# psg-dual.net
KiCad netlist of a schematic drawn in EAGLE
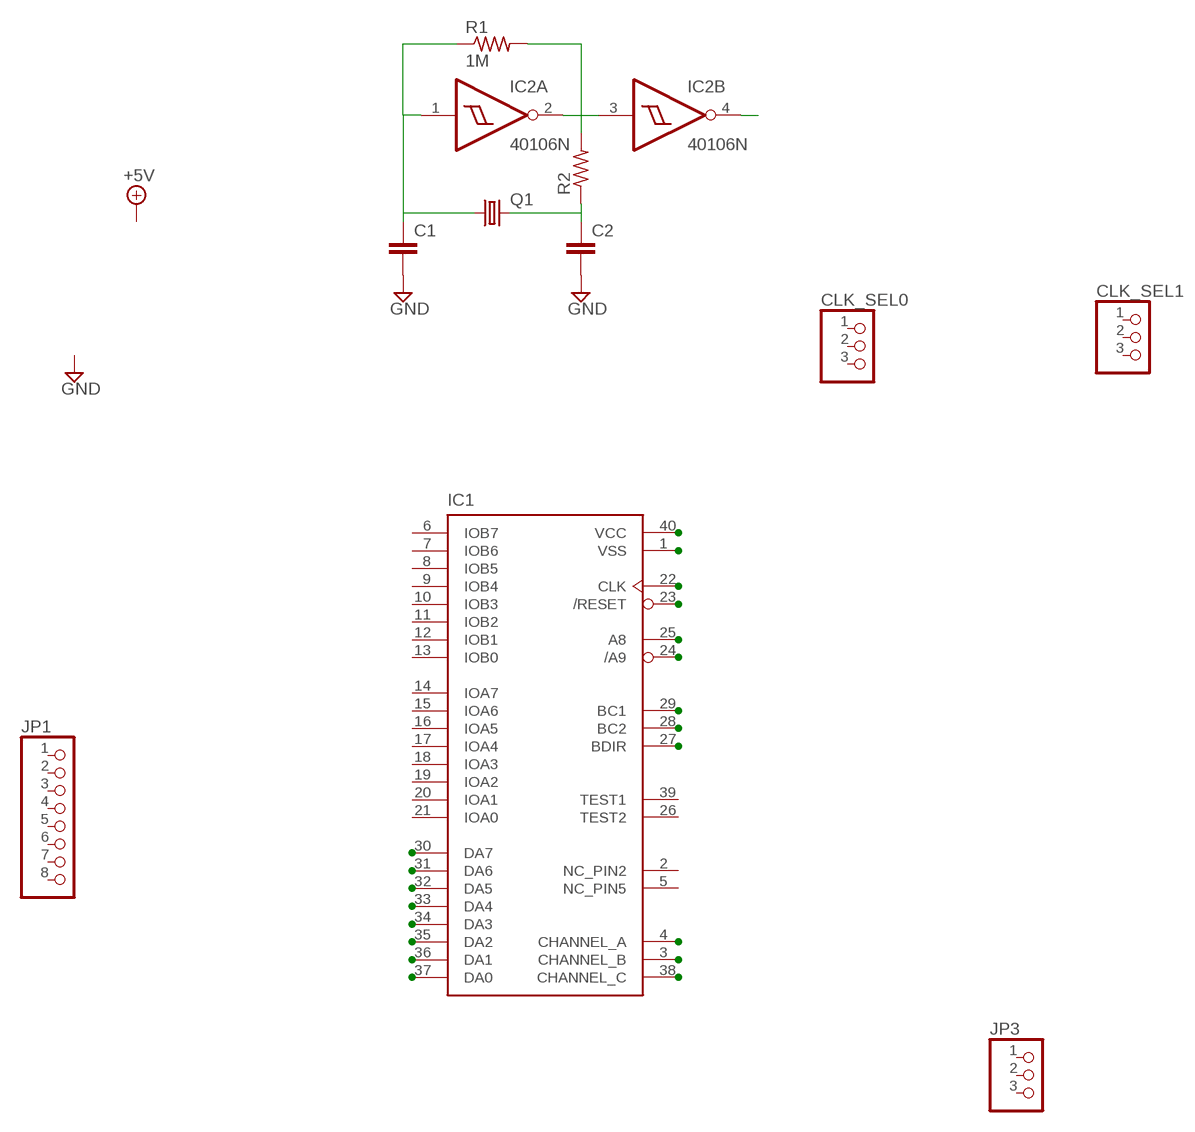
[diagram p0: schematic, sheet 1]

(export (version "E")
  (design (tool "Eeschema 10.0.6"))
  (components
    (comp (ref "C1")
      (value "050X030_0252")
      (footprint "eagle-import:050X030_025_2")
      (libsource (lib "eagle-import") (part "050X030_0252"))
    )
    (comp (ref "C2")
      (value "050X030_0252")
      (footprint "eagle-import:050X030_025_2")
      (libsource (lib "eagle-import") (part "050X030_0252"))
    )
    (comp (ref "CLK_SEL0")
      (value "PINHD-1X3")
      (footprint "eagle-import:1X03")
      (libsource (lib "eagle-import") (part "PINHD-1X3"))
    )
    (comp (ref "CLK_SEL1")
      (value "PINHD-1X3")
      (footprint "eagle-import:1X03")
      (libsource (lib "eagle-import") (part "PINHD-1X3"))
    )
    (comp (ref "IC1")
      (value "AY-3-8910")
      (footprint "eagle-import:DIL40")
      (libsource (lib "eagle-import") (part "AY-3-8910"))
    )
    (comp (ref "IC2")
      (value "40106N")
      (footprint "eagle-import:DIL14")
      (libsource (lib "eagle-import") (part "40106N"))
    )
    (comp (ref "JP1")
      (value "PINHD-1X8")
      (footprint "eagle-import:1X08")
      (libsource (lib "eagle-import") (part "PINHD-1X8"))
    )
    (comp (ref "JP3")
      (value "PINHD-1X3")
      (footprint "eagle-import:1X03")
      (libsource (lib "eagle-import") (part "PINHD-1X3"))
    )
    (comp (ref "Q1")
      (value "CRYSTALHC18U-V")
      (footprint "eagle-import:HC18U-V")
      (libsource (lib "eagle-import") (part "CRYSTALHC18U-V"))
    )
    (comp (ref "R1")
      (value "1M")
      (footprint "eagle-import:R0207_3")
      (libsource (lib "eagle-import") (part "6MM.3"))
    )
    (comp (ref "R2")
      (value "6MM.3")
      (footprint "eagle-import:R0207_3")
      (libsource (lib "eagle-import") (part "6MM.3"))
    )
  )
  (nets
    (net (code "2") (name "/VCC") (class "Default")
      (node (ref "IC1") (pin "40") (pinfunction "VCC_40") (pintype "power_in"))
    )
    (net (code "3") (name "/VSS") (class "Default")
      (node (ref "IC1") (pin "1") (pinfunction "VSS_1") (pintype "power_in"))
    )
    (net (code "4") (name "GND") (class "Default")
      (node (ref "C1") (pin "2") (pinfunction "2_2") (pintype "passive"))
      (node (ref "C2") (pin "2") (pinfunction "2_2") (pintype "passive"))
    )
    (net (code "5") (name "Net-(C2-Pad1)") (class "Default")
      (node (ref "C2") (pin "1") (pinfunction "1_1") (pintype "passive"))
      (node (ref "Q1") (pin "2") (pinfunction "2_2") (pintype "passive"))
      (node (ref "R2") (pin "1") (pinfunction "1_1") (pintype "passive"))
    )
    (net (code "6") (name "Net-(IC2A-I)") (class "Default")
      (node (ref "C1") (pin "1") (pinfunction "1_1") (pintype "passive"))
      (node (ref "IC2") (pin "1") (pinfunction "I_1") (pintype "input"))
      (node (ref "Q1") (pin "1") (pinfunction "1_1") (pintype "passive"))
      (node (ref "R1") (pin "1") (pinfunction "1_1") (pintype "passive"))
    )
    (net (code "7") (name "Net-(IC2A-O)") (class "Default")
      (node (ref "IC2") (pin "2") (pinfunction "O_2") (pintype "output"))
      (node (ref "IC2") (pin "3") (pinfunction "I_3") (pintype "input"))
      (node (ref "R1") (pin "2") (pinfunction "2_2") (pintype "passive"))
      (node (ref "R2") (pin "2") (pinfunction "2_2") (pintype "passive"))
    )
    (net (code "8") (name "unconnected-(CLK_SEL0-Pad1)") (class "Default")
      (node (ref "CLK_SEL0") (pin "1") (pinfunction "1_1") (pintype "passive"))
    )
    (net (code "9") (name "unconnected-(CLK_SEL0-Pad2)") (class "Default")
      (node (ref "CLK_SEL0") (pin "2") (pinfunction "2_2") (pintype "passive"))
    )
    (net (code "10") (name "unconnected-(CLK_SEL0-Pad3)") (class "Default")
      (node (ref "CLK_SEL0") (pin "3") (pinfunction "3_3") (pintype "passive"))
    )
    (net (code "11") (name "unconnected-(CLK_SEL1-Pad1)") (class "Default")
      (node (ref "CLK_SEL1") (pin "1") (pinfunction "1_1") (pintype "passive"))
    )
    (net (code "12") (name "unconnected-(CLK_SEL1-Pad2)") (class "Default")
      (node (ref "CLK_SEL1") (pin "2") (pinfunction "2_2") (pintype "passive"))
    )
    (net (code "13") (name "unconnected-(CLK_SEL1-Pad3)") (class "Default")
      (node (ref "CLK_SEL1") (pin "3") (pinfunction "3_3") (pintype "passive"))
    )
    (net (code "14") (name "unconnected-(IC1-A8-Pad25)") (class "Default")
      (node (ref "IC1") (pin "25") (pinfunction "A8_25") (pintype "bidirectional"))
    )
    (net (code "15") (name "unconnected-(IC1-BC1-Pad29)") (class "Default")
      (node (ref "IC1") (pin "29") (pinfunction "BC1_29") (pintype "input"))
    )
    (net (code "16") (name "unconnected-(IC1-BC2-Pad28)") (class "Default")
      (node (ref "IC1") (pin "28") (pinfunction "BC2_28") (pintype "input"))
    )
    (net (code "17") (name "unconnected-(IC1-BDIR-Pad27)") (class "Default")
      (node (ref "IC1") (pin "27") (pinfunction "BDIR_27") (pintype "input"))
    )
    (net (code "18") (name "unconnected-(IC1-CHANNEL_A-Pad4)") (class "Default")
      (node (ref "IC1") (pin "4") (pinfunction "CHANNEL_A_4") (pintype "output"))
    )
    (net (code "19") (name "unconnected-(IC1-CHANNEL_B-Pad3)") (class "Default")
      (node (ref "IC1") (pin "3") (pinfunction "CHANNEL_B_3") (pintype "output"))
    )
    (net (code "20") (name "unconnected-(IC1-CHANNEL_C-Pad38)") (class "Default")
      (node (ref "IC1") (pin "38") (pinfunction "CHANNEL_C_38") (pintype "output"))
    )
    (net (code "21") (name "unconnected-(IC1-CLK-Pad22)") (class "Default")
      (node (ref "IC1") (pin "22") (pinfunction "CLK_22") (pintype "input"))
    )
    (net (code "22") (name "unconnected-(IC1-DA0-Pad37)") (class "Default")
      (node (ref "IC1") (pin "37") (pinfunction "DA0_37") (pintype "bidirectional"))
    )
    (net (code "23") (name "unconnected-(IC1-DA1-Pad36)") (class "Default")
      (node (ref "IC1") (pin "36") (pinfunction "DA1_36") (pintype "bidirectional"))
    )
    (net (code "24") (name "unconnected-(IC1-DA2-Pad35)") (class "Default")
      (node (ref "IC1") (pin "35") (pinfunction "DA2_35") (pintype "bidirectional"))
    )
    (net (code "25") (name "unconnected-(IC1-DA3-Pad34)") (class "Default")
      (node (ref "IC1") (pin "34") (pinfunction "DA3_34") (pintype "bidirectional"))
    )
    (net (code "26") (name "unconnected-(IC1-DA4-Pad33)") (class "Default")
      (node (ref "IC1") (pin "33") (pinfunction "DA4_33") (pintype "bidirectional"))
    )
    (net (code "27") (name "unconnected-(IC1-DA5-Pad32)") (class "Default")
      (node (ref "IC1") (pin "32") (pinfunction "DA5_32") (pintype "bidirectional"))
    )
    (net (code "28") (name "unconnected-(IC1-DA6-Pad31)") (class "Default")
      (node (ref "IC1") (pin "31") (pinfunction "DA6_31") (pintype "bidirectional"))
    )
    (net (code "29") (name "unconnected-(IC1-DA7-Pad30)") (class "Default")
      (node (ref "IC1") (pin "30") (pinfunction "DA7_30") (pintype "bidirectional"))
    )
    (net (code "30") (name "unconnected-(IC1-IOA0-Pad21)") (class "Default")
      (node (ref "IC1") (pin "21") (pinfunction "IOA0_21") (pintype "bidirectional"))
    )
    (net (code "31") (name "unconnected-(IC1-IOA1-Pad20)") (class "Default")
      (node (ref "IC1") (pin "20") (pinfunction "IOA1_20") (pintype "bidirectional"))
    )
    (net (code "32") (name "unconnected-(IC1-IOA2-Pad19)") (class "Default")
      (node (ref "IC1") (pin "19") (pinfunction "IOA2_19") (pintype "bidirectional"))
    )
    (net (code "33") (name "unconnected-(IC1-IOA3-Pad18)") (class "Default")
      (node (ref "IC1") (pin "18") (pinfunction "IOA3_18") (pintype "bidirectional"))
    )
    (net (code "34") (name "unconnected-(IC1-IOA4-Pad17)") (class "Default")
      (node (ref "IC1") (pin "17") (pinfunction "IOA4_17") (pintype "bidirectional"))
    )
    (net (code "35") (name "unconnected-(IC1-IOA5-Pad16)") (class "Default")
      (node (ref "IC1") (pin "16") (pinfunction "IOA5_16") (pintype "bidirectional"))
    )
    (net (code "36") (name "unconnected-(IC1-IOA6-Pad15)") (class "Default")
      (node (ref "IC1") (pin "15") (pinfunction "IOA6_15") (pintype "bidirectional"))
    )
    (net (code "37") (name "unconnected-(IC1-IOA7-Pad14)") (class "Default")
      (node (ref "IC1") (pin "14") (pinfunction "IOA7_14") (pintype "bidirectional"))
    )
    (net (code "38") (name "unconnected-(IC1-IOB0-Pad13)") (class "Default")
      (node (ref "IC1") (pin "13") (pinfunction "IOB0_13") (pintype "bidirectional"))
    )
    (net (code "39") (name "unconnected-(IC1-IOB1-Pad12)") (class "Default")
      (node (ref "IC1") (pin "12") (pinfunction "IOB1_12") (pintype "bidirectional"))
    )
    (net (code "40") (name "unconnected-(IC1-IOB2-Pad11)") (class "Default")
      (node (ref "IC1") (pin "11") (pinfunction "IOB2_11") (pintype "bidirectional"))
    )
    (net (code "41") (name "unconnected-(IC1-IOB3-Pad10)") (class "Default")
      (node (ref "IC1") (pin "10") (pinfunction "IOB3_10") (pintype "bidirectional"))
    )
    (net (code "42") (name "unconnected-(IC1-IOB4-Pad9)") (class "Default")
      (node (ref "IC1") (pin "9") (pinfunction "IOB4_9") (pintype "bidirectional"))
    )
    (net (code "43") (name "unconnected-(IC1-IOB5-Pad8)") (class "Default")
      (node (ref "IC1") (pin "8") (pinfunction "IOB5_8") (pintype "bidirectional"))
    )
    (net (code "44") (name "unconnected-(IC1-IOB6-Pad7)") (class "Default")
      (node (ref "IC1") (pin "7") (pinfunction "IOB6_7") (pintype "bidirectional"))
    )
    (net (code "45") (name "unconnected-(IC1-IOB7-Pad6)") (class "Default")
      (node (ref "IC1") (pin "6") (pinfunction "IOB7_6") (pintype "bidirectional"))
    )
    (net (code "46") (name "unconnected-(IC1-NC_PIN2-Pad2)") (class "Default")
      (node (ref "IC1") (pin "2") (pinfunction "NC_PIN2_2") (pintype "no_connect"))
    )
    (net (code "47") (name "unconnected-(IC1-NC_PIN5-Pad5)") (class "Default")
      (node (ref "IC1") (pin "5") (pinfunction "NC_PIN5_5") (pintype "bidirectional"))
    )
    (net (code "48") (name "unconnected-(IC1-TEST1-Pad39)") (class "Default")
      (node (ref "IC1") (pin "39") (pinfunction "TEST1_39") (pintype "no_connect"))
    )
    (net (code "49") (name "unconnected-(IC1-TEST2-Pad26)") (class "Default")
      (node (ref "IC1") (pin "26") (pinfunction "TEST2_26") (pintype "no_connect"))
    )
    (net (code "50") (name "unconnected-(IC1-{slash}A9-Pad24)") (class "Default")
      (node (ref "IC1") (pin "24") (pinfunction "/A9_24") (pintype "bidirectional"))
    )
    (net (code "51") (name "unconnected-(IC1-{slash}RESET-Pad23)") (class "Default")
      (node (ref "IC1") (pin "23") (pinfunction "/RESET_23") (pintype "input"))
    )
    (net (code "52") (name "unconnected-(IC2B-O-Pad4)") (class "Default")
      (node (ref "IC2") (pin "4") (pinfunction "O_4") (pintype "output"))
    )
    (net (code "53") (name "unconnected-(JP1-Pad1)") (class "Default")
      (node (ref "JP1") (pin "1") (pinfunction "1_1") (pintype "passive"))
    )
    (net (code "54") (name "unconnected-(JP1-Pad2)") (class "Default")
      (node (ref "JP1") (pin "2") (pinfunction "2_2") (pintype "passive"))
    )
    (net (code "55") (name "unconnected-(JP1-Pad3)") (class "Default")
      (node (ref "JP1") (pin "3") (pinfunction "3_3") (pintype "passive"))
    )
    (net (code "56") (name "unconnected-(JP1-Pad4)") (class "Default")
      (node (ref "JP1") (pin "4") (pinfunction "4_4") (pintype "passive"))
    )
    (net (code "57") (name "unconnected-(JP1-Pad5)") (class "Default")
      (node (ref "JP1") (pin "5") (pinfunction "5_5") (pintype "passive"))
    )
    (net (code "58") (name "unconnected-(JP1-Pad6)") (class "Default")
      (node (ref "JP1") (pin "6") (pinfunction "6_6") (pintype "passive"))
    )
    (net (code "59") (name "unconnected-(JP1-Pad7)") (class "Default")
      (node (ref "JP1") (pin "7") (pinfunction "7_7") (pintype "passive"))
    )
    (net (code "60") (name "unconnected-(JP1-Pad8)") (class "Default")
      (node (ref "JP1") (pin "8") (pinfunction "8_8") (pintype "passive"))
    )
    (net (code "61") (name "unconnected-(JP3-Pad1)") (class "Default")
      (node (ref "JP3") (pin "1") (pinfunction "1_1") (pintype "passive"))
    )
    (net (code "62") (name "unconnected-(JP3-Pad2)") (class "Default")
      (node (ref "JP3") (pin "2") (pinfunction "2_2") (pintype "passive"))
    )
    (net (code "63") (name "unconnected-(JP3-Pad3)") (class "Default")
      (node (ref "JP3") (pin "3") (pinfunction "3_3") (pintype "passive"))
    )
  )
)
